# bytexplore_devboard.net
KiCad netlist of a schematic drawn in EAGLE
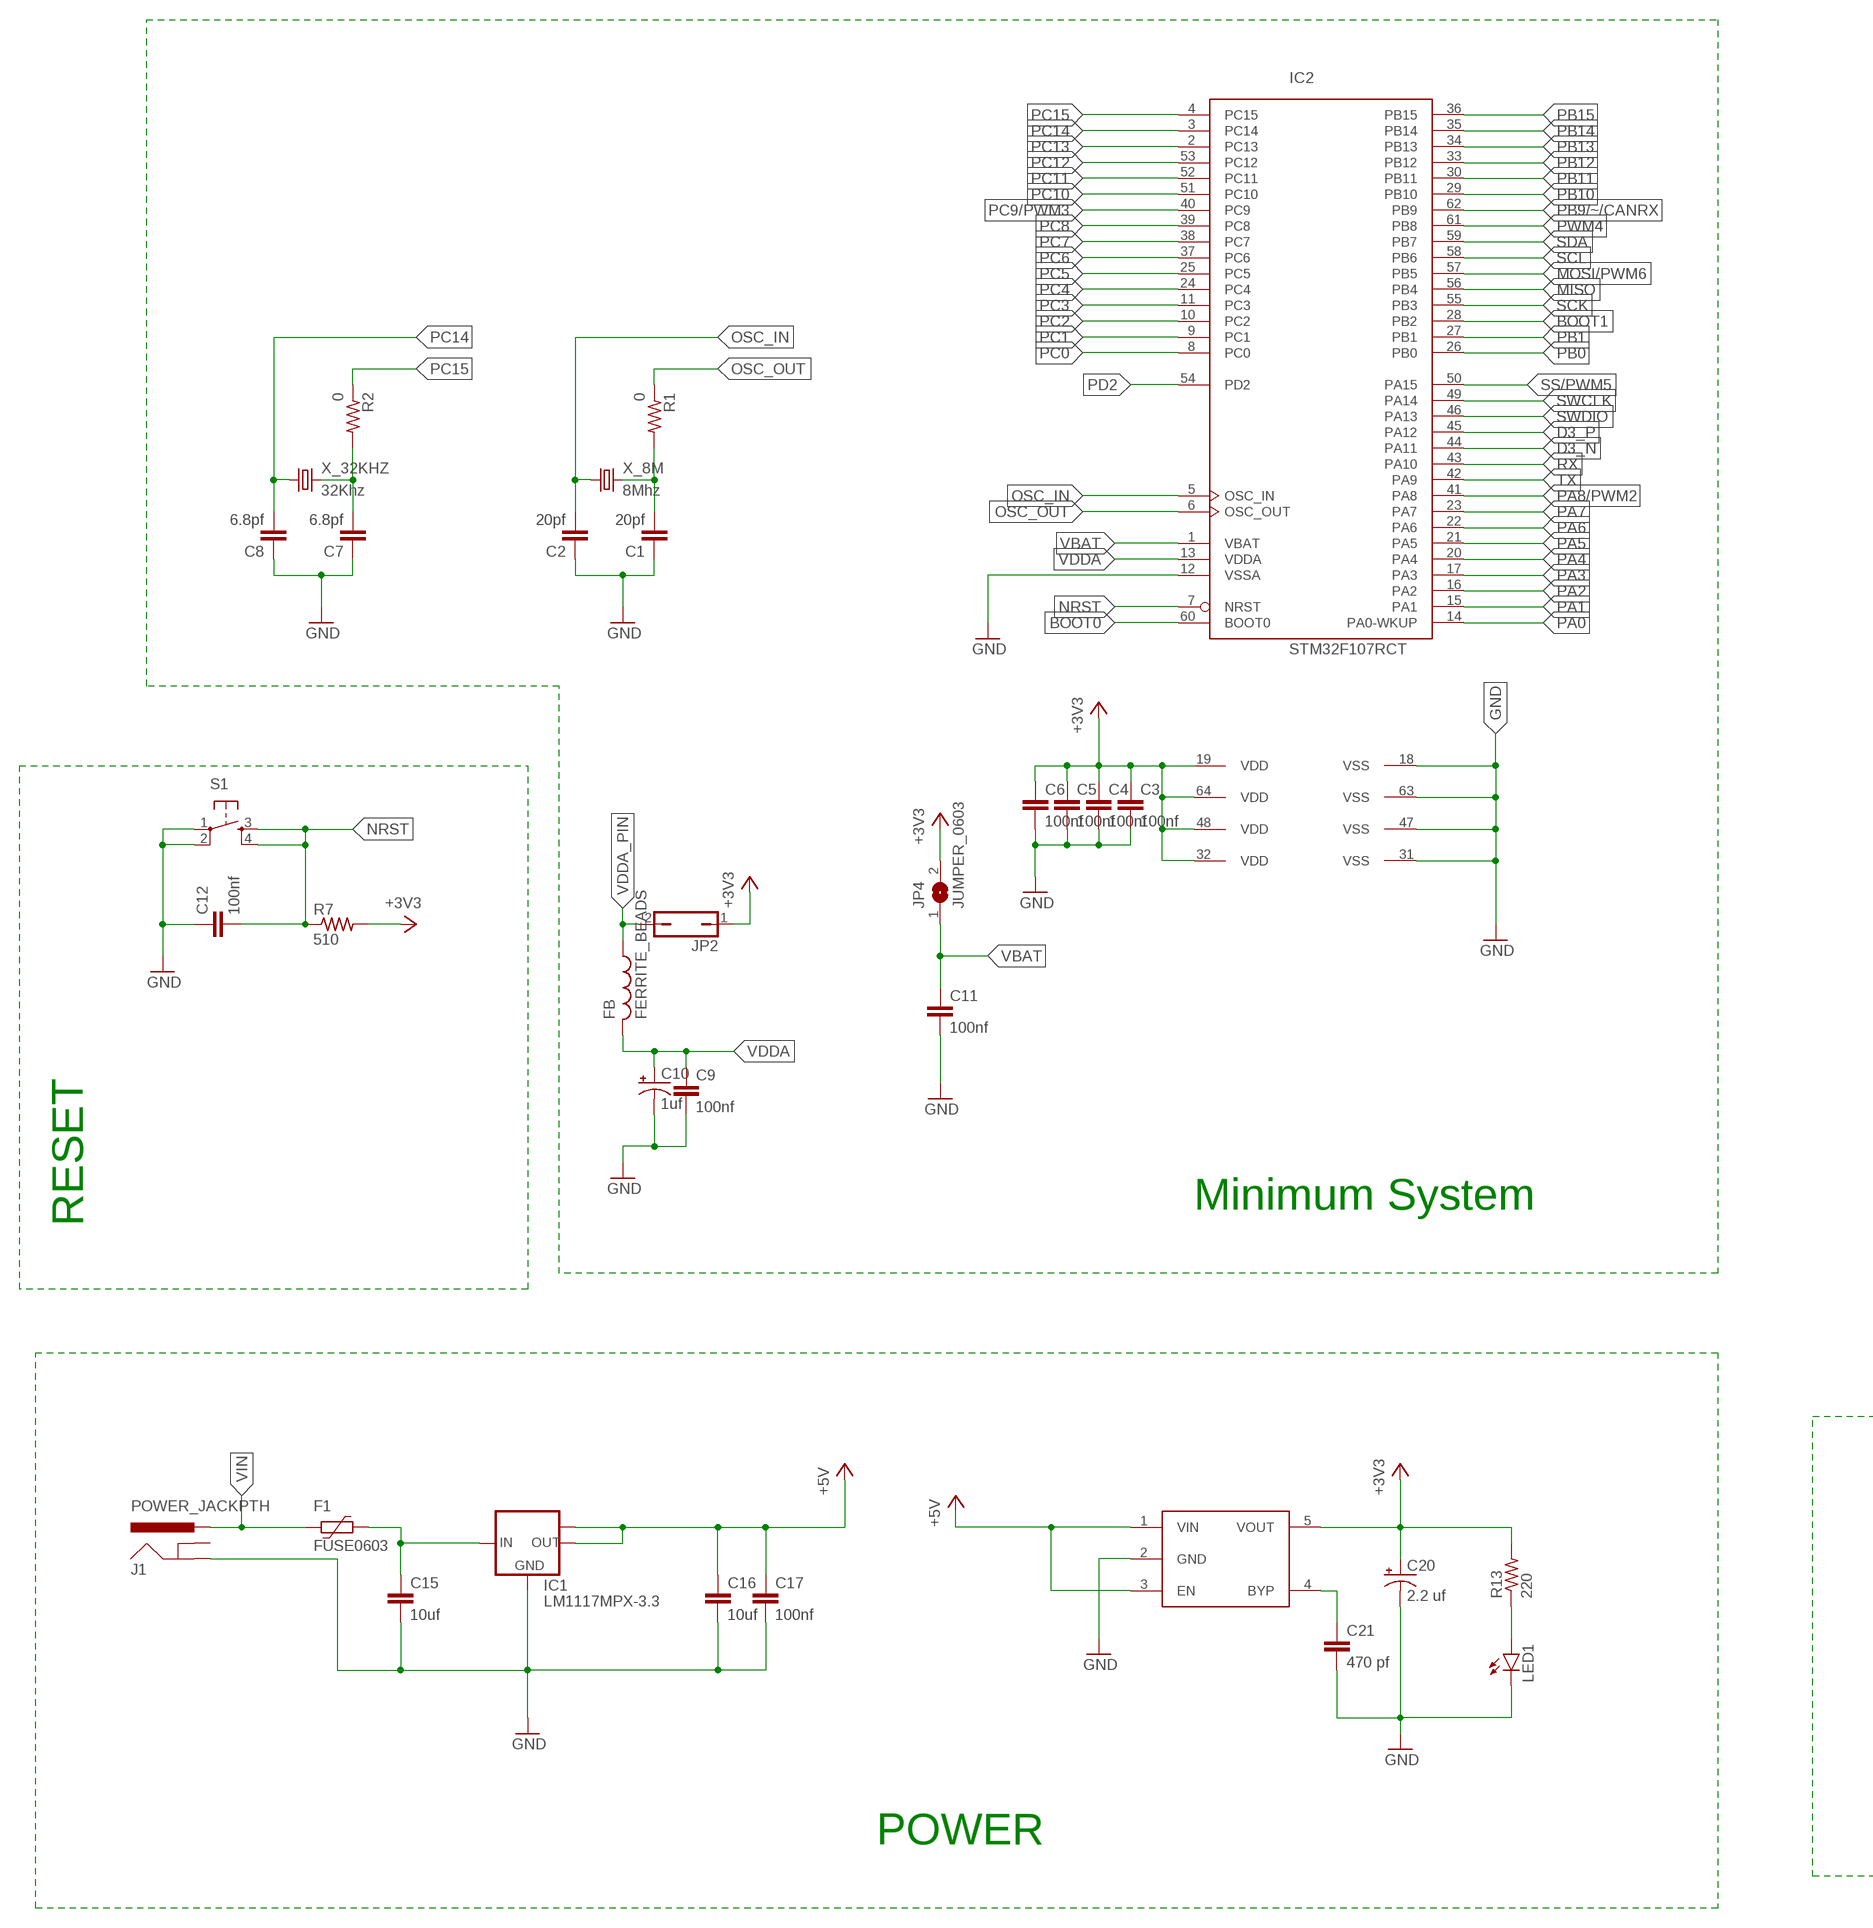
[diagram p0: schematic, sheet 1, part 1 of 2]
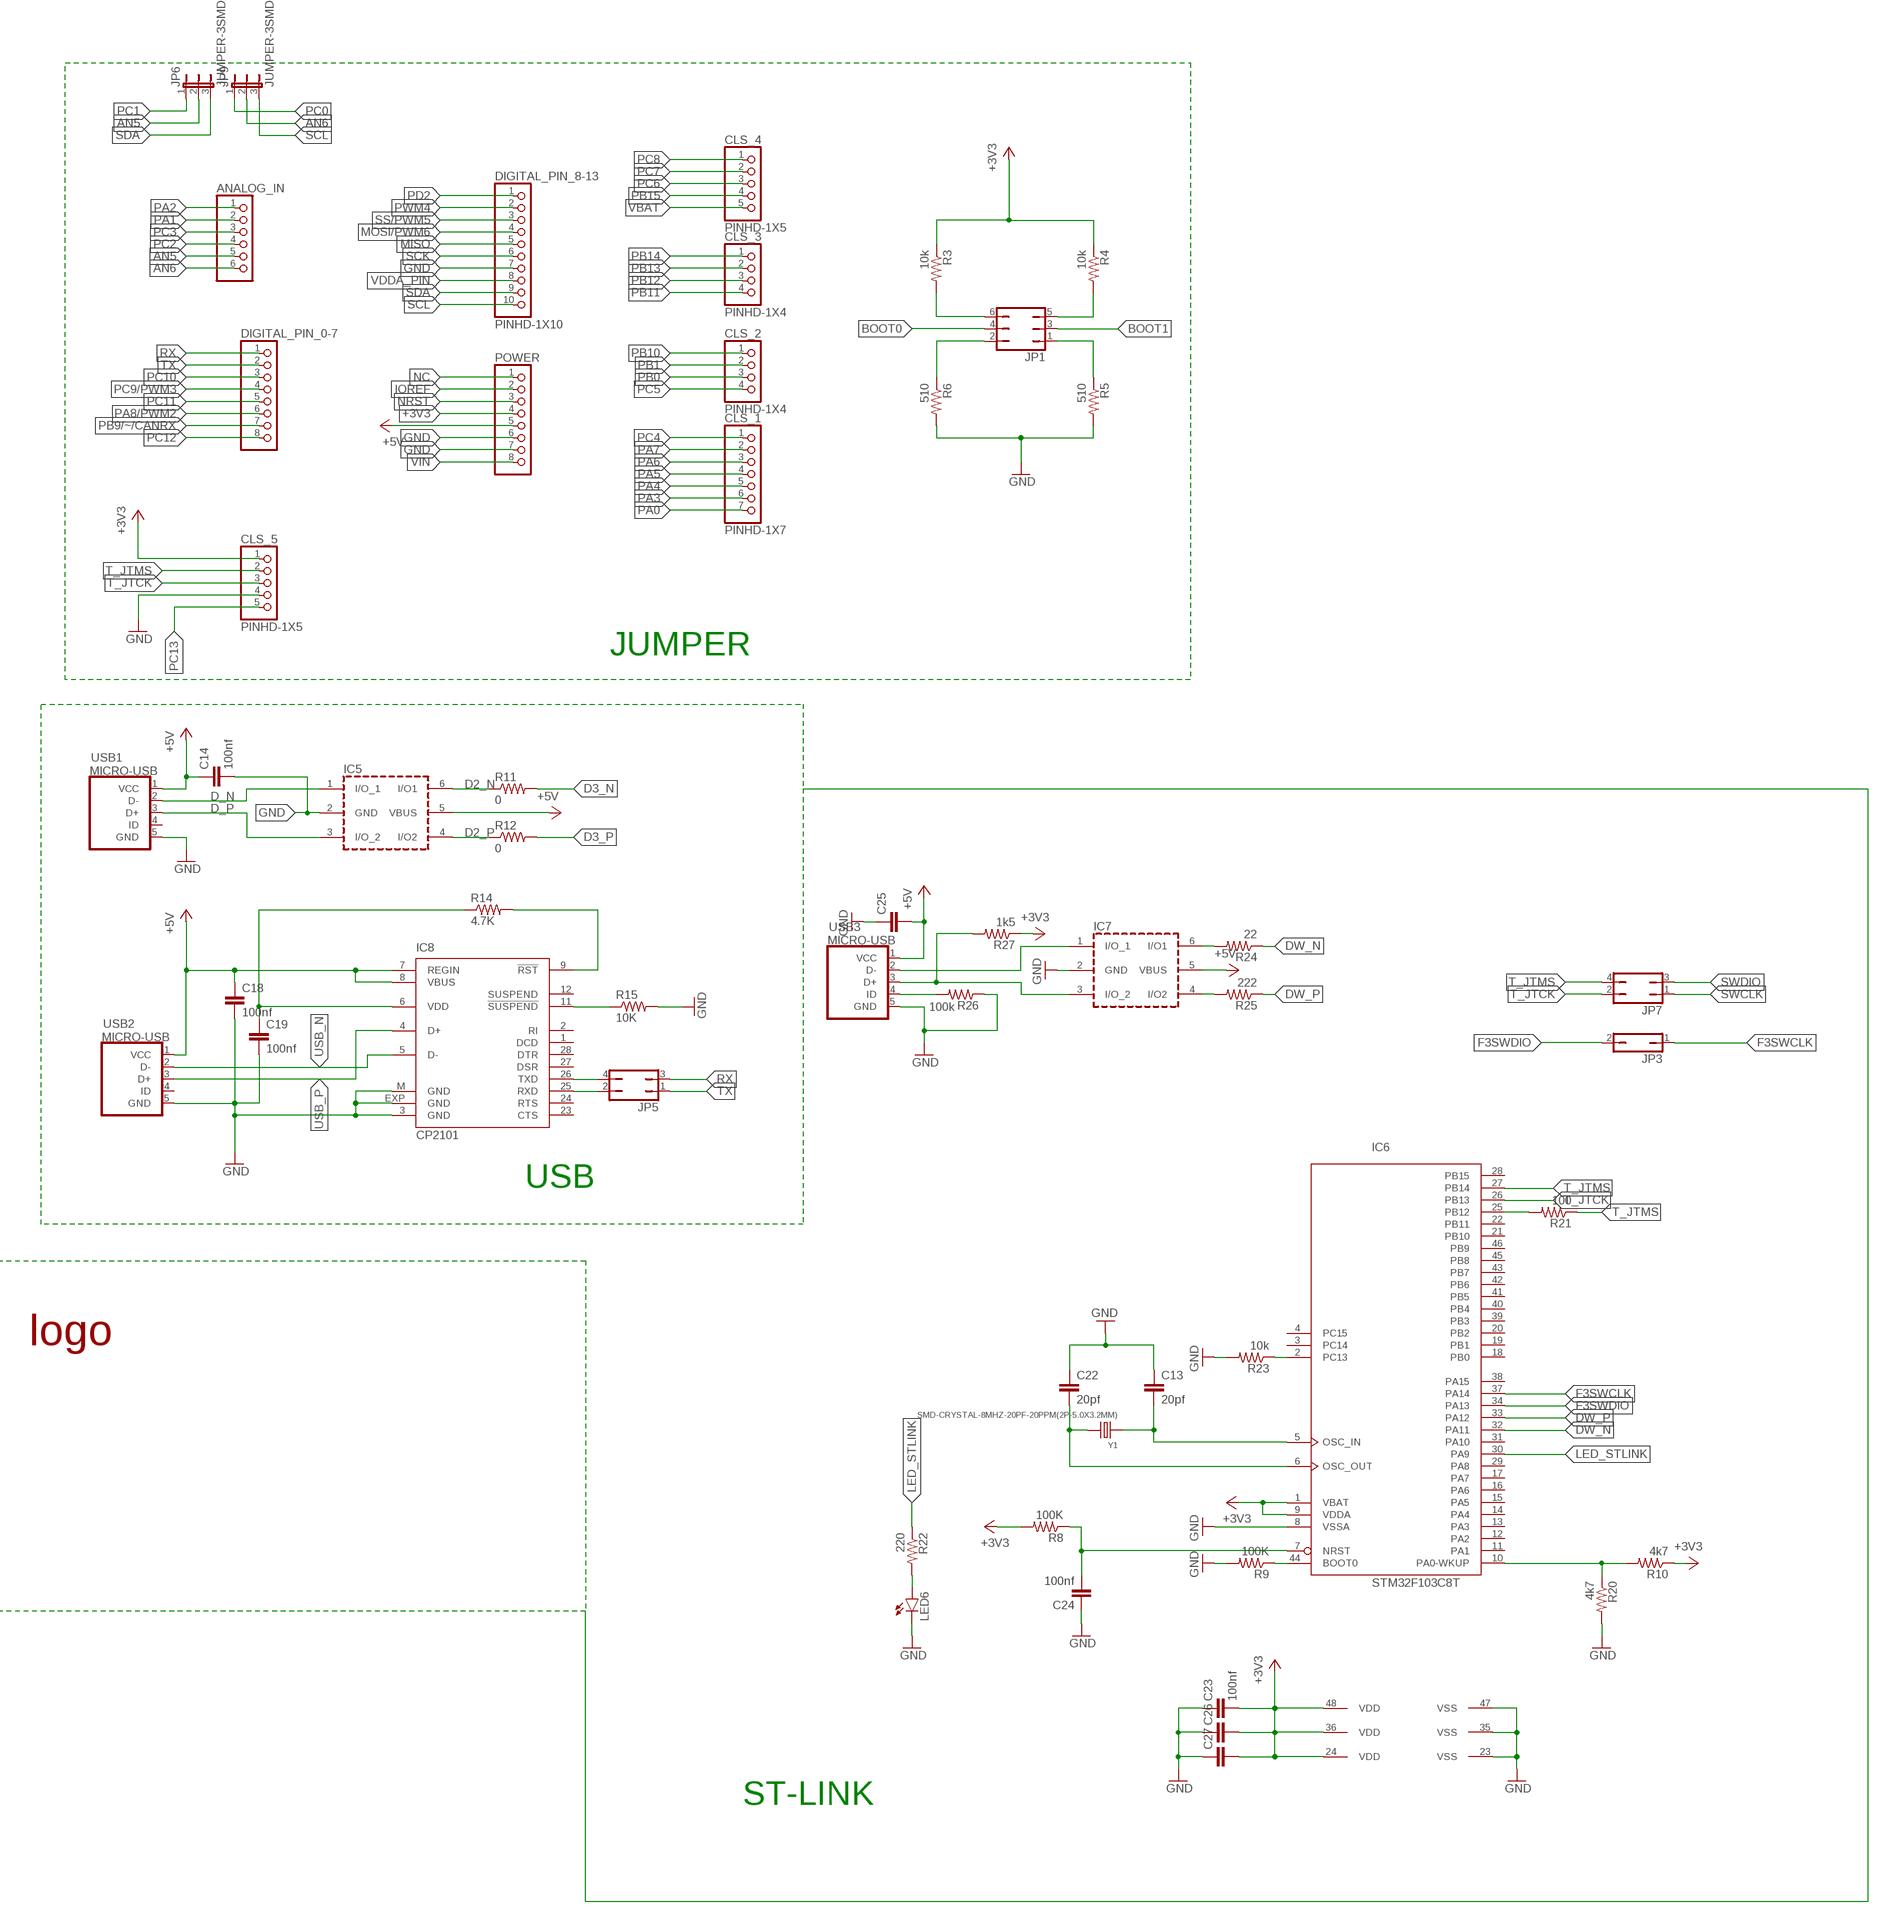
[diagram p1: schematic, sheet 1, part 2 of 2]

(export (version "E")
  (design (tool "Eeschema 10.0.6"))
  (components
    (comp (ref "ANALOG_IN")
      (value "PINHD-1X6B")
      (footprint "eagle-import:1X06-BIG")
      (libsource (lib "eagle-import") (part "PINHD-1X6B"))
    )
    (comp (ref "C1")
      (value "20pf")
      (footprint "eagle-import:C0603K")
      (libsource (lib "eagle-import") (part "C-EUC0603K"))
    )
    (comp (ref "C2")
      (value "20pf")
      (footprint "eagle-import:C0603K")
      (libsource (lib "eagle-import") (part "C-EUC0603K"))
    )
    (comp (ref "C3")
      (value "100nf")
      (footprint "eagle-import:C0603K")
      (libsource (lib "eagle-import") (part "C-EUC0603K"))
    )
    (comp (ref "C4")
      (value "100nf")
      (footprint "eagle-import:C0603K")
      (libsource (lib "eagle-import") (part "C-EUC0603K"))
    )
    (comp (ref "C5")
      (value "100nf")
      (footprint "eagle-import:C0603K")
      (libsource (lib "eagle-import") (part "C-EUC0603K"))
    )
    (comp (ref "C6")
      (value "100nf")
      (footprint "eagle-import:C0603K")
      (libsource (lib "eagle-import") (part "C-EUC0603K"))
    )
    (comp (ref "C7")
      (value "6.8pf")
      (footprint "eagle-import:C0603K")
      (libsource (lib "eagle-import") (part "C-EUC0603K"))
    )
    (comp (ref "C8")
      (value "6.8pf")
      (footprint "eagle-import:C0603K")
      (libsource (lib "eagle-import") (part "C-EUC0603K"))
    )
    (comp (ref "C9")
      (value "100nf")
      (footprint "eagle-import:C0603K")
      (libsource (lib "eagle-import") (part "C-EUC0603K"))
    )
    (comp (ref "C10")
      (value "1uf")
      (footprint "eagle-import:SMC_B")
      (libsource (lib "eagle-import") (part "CPOL-USSMCB"))
    )
    (comp (ref "C11")
      (value "100nf")
      (footprint "eagle-import:C0603K")
      (libsource (lib "eagle-import") (part "C-EUC0603K"))
    )
    (comp (ref "C12")
      (value "100nf")
      (footprint "eagle-import:C0603K")
      (libsource (lib "eagle-import") (part "C-EUC0603K"))
    )
    (comp (ref "C13")
      (value "20pf")
      (footprint "eagle-import:C0603")
      (libsource (lib "eagle-import") (part "C-EUC0603"))
    )
    (comp (ref "C14")
      (value "100nf")
      (footprint "eagle-import:C0603K")
      (libsource (lib "eagle-import") (part "C-EUC0603K"))
    )
    (comp (ref "C15")
      (value "10uf")
      (footprint "eagle-import:C0603")
      (libsource (lib "eagle-import") (part "C-EUC0603"))
    )
    (comp (ref "C16")
      (value "10uf")
      (footprint "eagle-import:C0603")
      (libsource (lib "eagle-import") (part "C-EUC0603"))
    )
    (comp (ref "C17")
      (value "100nf")
      (footprint "eagle-import:C0603")
      (libsource (lib "eagle-import") (part "C-EUC0603"))
    )
    (comp (ref "C18")
      (value "100nf")
      (footprint "eagle-import:C0603K")
      (libsource (lib "eagle-import") (part "C-EUC0603K"))
    )
    (comp (ref "C19")
      (value "100nf")
      (footprint "eagle-import:C0603K")
      (libsource (lib "eagle-import") (part "C-EUC0603K"))
    )
    (comp (ref "C20")
      (value "2.2 uf")
      (footprint "eagle-import:SMC_A")
      (libsource (lib "eagle-import") (part "CPOL-USSMCA"))
    )
    (comp (ref "C21")
      (value "470 pf")
      (footprint "eagle-import:C0603")
      (libsource (lib "eagle-import") (part "C-EUC0603"))
    )
    (comp (ref "C22")
      (value "20pf")
      (footprint "eagle-import:C0603")
      (libsource (lib "eagle-import") (part "C-EUC0603"))
    )
    (comp (ref "C23")
      (value "100nf")
      (footprint "eagle-import:C0603")
      (libsource (lib "eagle-import") (part "C-EUC0603"))
    )
    (comp (ref "C24")
      (value "100nf")
      (footprint "eagle-import:C0603")
      (libsource (lib "eagle-import") (part "C-EUC0603"))
    )
    (comp (ref "C25")
      (value "C-EUC0603")
      (footprint "eagle-import:C0603")
      (libsource (lib "eagle-import") (part "C-EUC0603"))
    )
    (comp (ref "C26")
      (value "C-EUC0603")
      (footprint "eagle-import:C0603")
      (libsource (lib "eagle-import") (part "C-EUC0603"))
    )
    (comp (ref "C27")
      (value "C-EUC0603")
      (footprint "eagle-import:C0603")
      (libsource (lib "eagle-import") (part "C-EUC0603"))
    )
    (comp (ref "CLS_1")
      (value "PINHD-1X7")
      (footprint "eagle-import:1X07-BIG")
      (libsource (lib "eagle-import") (part "PINHD-1X7"))
    )
    (comp (ref "CLS_2")
      (value "PINHD-1X4")
      (footprint "eagle-import:1X04-BIG")
      (libsource (lib "eagle-import") (part "PINHD-1X4"))
    )
    (comp (ref "CLS_3")
      (value "PINHD-1X4")
      (footprint "eagle-import:1X04-BIG")
      (libsource (lib "eagle-import") (part "PINHD-1X4"))
    )
    (comp (ref "CLS_4")
      (value "PINHD-1X5")
      (footprint "eagle-import:1X05-BIG")
      (libsource (lib "eagle-import") (part "PINHD-1X5"))
    )
    (comp (ref "CLS_5")
      (value "PINHD-1X5")
      (footprint "eagle-import:1X05-BIG")
      (libsource (lib "eagle-import") (part "PINHD-1X5"))
    )
    (comp (ref "DIGITAL_PIN_0-7")
      (value "PINHD-1X8BIG")
      (footprint "eagle-import:1X08-BIG")
      (libsource (lib "eagle-import") (part "PINHD-1X8BIG"))
    )
    (comp (ref "DIGITAL_PIN_8-13")
      (value "PINHD-1X10")
      (footprint "eagle-import:1X10-BIG")
      (libsource (lib "eagle-import") (part "PINHD-1X10"))
    )
    (comp (ref "F1")
      (value "FUSE0603")
      (footprint "eagle-import:R0603")
      (libsource (lib "eagle-import") (part "FUSE0603"))
    )
    (comp (ref "FB")
      (value "FERRITE_BEADS")
      (footprint "eagle-import:R0603")
      (libsource (lib "eagle-import") (part "FERRITE_BEADS"))
    )
    (comp (ref "IC1")
      (value "LM1117MPX-3.3")
      (footprint "eagle-import:SOT223")
      (libsource (lib "eagle-import") (part "LM1117MPX-3.3"))
    )
    (comp (ref "IC2")
      (value "STM32F107RCT")
      (footprint "eagle-import:LQFP64")
      (libsource (lib "eagle-import") (part "STM32F107RTC"))
    )
    (comp (ref "IC4")
      (value "MIC5219")
      (footprint "eagle-import:SOT-23-5")
      (libsource (lib "eagle-import") (part "MIC5219"))
    )
    (comp (ref "IC5")
      (value "USBLC6-2SC6")
      (footprint "eagle-import:SOT-23-6L")
      (libsource (lib "eagle-import") (part "USBLC6-2SC6"))
    )
    (comp (ref "IC6")
      (value "STM32F103C8T")
      (footprint "eagle-import:LQFP48")
      (libsource (lib "eagle-import") (part "STM32F103CT8"))
    )
    (comp (ref "IC7")
      (value "USBLC6-2SC6")
      (footprint "eagle-import:SOT-23-6L")
      (libsource (lib "eagle-import") (part "USBLC6-2SC6"))
    )
    (comp (ref "IC8")
      (value "CP2101")
      (footprint "eagle-import:MLP28")
      (libsource (lib "eagle-import") (part "CP2101"))
    )
    (comp (ref "J1")
      (value "POWER_JACKPTH")
      (footprint "eagle-import:POWER_JACK_PTH")
      (libsource (lib "eagle-import") (part "POWER_JACKPTH"))
    )
    (comp (ref "JP1")
      (value "JP3Q")
      (footprint "eagle-import:JP3Q")
      (libsource (lib "eagle-import") (part "JP3Q"))
    )
    (comp (ref "JP2")
      (value "JP1Q")
      (footprint "eagle-import:JP1")
      (libsource (lib "eagle-import") (part "JP1Q"))
    )
    (comp (ref "JP3")
      (value "JP1Q")
      (footprint "eagle-import:JP1")
      (libsource (lib "eagle-import") (part "JP1Q"))
    )
    (comp (ref "JP4")
      (value "JUMPER_0603")
      (footprint "eagle-import:R0603")
      (libsource (lib "eagle-import") (part "JUMPER_0603"))
    )
    (comp (ref "JP5")
      (value "JP2Q")
      (footprint "eagle-import:JP2Q")
      (libsource (lib "eagle-import") (part "JP2Q"))
    )
    (comp (ref "JP6")
      (value "JUMPER-3SMD")
      (footprint "eagle-import:SJ_3")
      (libsource (lib "eagle-import") (part "JUMPER-3SMD"))
    )
    (comp (ref "JP7")
      (value "JP2Q")
      (footprint "eagle-import:JP2Q")
      (libsource (lib "eagle-import") (part "JP2Q"))
    )
    (comp (ref "JP9")
      (value "JUMPER-3SMD")
      (footprint "eagle-import:SJ_3")
      (libsource (lib "eagle-import") (part "JUMPER-3SMD"))
    )
    (comp (ref "LED1")
      (value "LEDSML0603")
      (footprint "eagle-import:SML0603")
      (libsource (lib "eagle-import") (part "LEDSML0603"))
    )
    (comp (ref "LED6")
      (value "LEDSML0603")
      (footprint "eagle-import:SML0603")
      (libsource (lib "eagle-import") (part "LEDSML0603"))
    )
    (comp (ref "POWER")
      (value "PINHD-1X8BIG")
      (footprint "eagle-import:1X08-BIG")
      (libsource (lib "eagle-import") (part "PINHD-1X8BIG"))
    )
    (comp (ref "R1")
      (value "0")
      (footprint "eagle-import:R0603")
      (libsource (lib "eagle-import") (part "R-US_R0603"))
    )
    (comp (ref "R2")
      (value "0")
      (footprint "eagle-import:R0603")
      (libsource (lib "eagle-import") (part "R-US_R0603"))
    )
    (comp (ref "R3")
      (value "10k")
      (footprint "eagle-import:R0603")
      (libsource (lib "eagle-import") (part "R-US_R0603"))
    )
    (comp (ref "R4")
      (value "10k")
      (footprint "eagle-import:R0603")
      (libsource (lib "eagle-import") (part "R-US_R0603"))
    )
    (comp (ref "R5")
      (value "510")
      (footprint "eagle-import:R0603")
      (libsource (lib "eagle-import") (part "R-US_R0603"))
    )
    (comp (ref "R6")
      (value "510")
      (footprint "eagle-import:R0603")
      (libsource (lib "eagle-import") (part "R-US_R0603"))
    )
    (comp (ref "R7")
      (value "510")
      (footprint "eagle-import:R0603")
      (libsource (lib "eagle-import") (part "R-US_R0603"))
    )
    (comp (ref "R8")
      (value "100K")
      (footprint "eagle-import:R0603")
      (libsource (lib "eagle-import") (part "R-US_R0603"))
    )
    (comp (ref "R9")
      (value "100K")
      (footprint "eagle-import:R0603")
      (libsource (lib "eagle-import") (part "R-US_R0603"))
    )
    (comp (ref "R10")
      (value "4k7")
      (footprint "eagle-import:R0603")
      (libsource (lib "eagle-import") (part "R-US_R0603"))
    )
    (comp (ref "R11")
      (value "0")
      (footprint "eagle-import:R0603")
      (libsource (lib "eagle-import") (part "R-US_R0603"))
    )
    (comp (ref "R12")
      (value "0")
      (footprint "eagle-import:R0603")
      (libsource (lib "eagle-import") (part "R-US_R0603"))
    )
    (comp (ref "R13")
      (value "220")
      (footprint "eagle-import:R0603")
      (libsource (lib "eagle-import") (part "R-US_R0603"))
    )
    (comp (ref "R14")
      (value "4.7K")
      (footprint "eagle-import:R0603")
      (libsource (lib "eagle-import") (part "R-US_R0603"))
    )
    (comp (ref "R15")
      (value "10K")
      (footprint "eagle-import:R0603")
      (libsource (lib "eagle-import") (part "R-US_R0603"))
    )
    (comp (ref "R20")
      (value "4k7")
      (footprint "eagle-import:R0603")
      (libsource (lib "eagle-import") (part "R-US_R0603"))
    )
    (comp (ref "R21")
      (value "100")
      (footprint "eagle-import:R0603")
      (libsource (lib "eagle-import") (part "R-US_R0603"))
    )
    (comp (ref "R22")
      (value "220")
      (footprint "eagle-import:R0603")
      (libsource (lib "eagle-import") (part "R-US_R0603"))
    )
    (comp (ref "R23")
      (value "10k")
      (footprint "eagle-import:R0603")
      (libsource (lib "eagle-import") (part "R-US_R0603"))
    )
    (comp (ref "R24")
      (value "22")
      (footprint "eagle-import:R0603")
      (libsource (lib "eagle-import") (part "R-US_R0603"))
    )
    (comp (ref "R25")
      (value "222")
      (footprint "eagle-import:R0603")
      (libsource (lib "eagle-import") (part "R-US_R0603"))
    )
    (comp (ref "R26")
      (value "100k")
      (footprint "eagle-import:R0603")
      (libsource (lib "eagle-import") (part "R-US_R0603"))
    )
    (comp (ref "R27")
      (value "1k5")
      (footprint "eagle-import:R0603")
      (libsource (lib "eagle-import") (part "R-US_R0603"))
    )
    (comp (ref "S1")
      (value "TAC_SWITCHPTH")
      (footprint "eagle-import:TACTILE-PTH")
      (libsource (lib "eagle-import") (part "TAC_SWITCHPTH"))
    )
    (comp (ref "U$1")
      (value "LOGO_PME2")
      (footprint "eagle-import:LOGO_PME2")
      (libsource (lib "eagle-import") (part "LOGO_PME2"))
    )
    (comp (ref "USB1")
      (value "MICRO-USB")
      (footprint "eagle-import:MICRO-USB")
      (libsource (lib "eagle-import") (part "MICRO-USB"))
    )
    (comp (ref "USB2")
      (value "MICRO-USB")
      (footprint "eagle-import:MICRO-USB")
      (libsource (lib "eagle-import") (part "MICRO-USB"))
    )
    (comp (ref "USB3")
      (value "MICRO-USB")
      (footprint "eagle-import:MICRO-USB")
      (libsource (lib "eagle-import") (part "MICRO-USB"))
    )
    (comp (ref "X_8M")
      (value "8Mhz")
      (footprint "eagle-import:HC49U70")
      (libsource (lib "eagle-import") (part "CRYSTALHC49U70"))
    )
    (comp (ref "X_32KHZ")
      (value "32Khz")
      (footprint "eagle-import:TC26H")
      (libsource (lib "eagle-import") (part "CRYSTALTC26H"))
    )
    (comp (ref "Y1")
      (value "SMD-CRYSTAL-8MHZ-20PF-20PPM(2P-5.0X3.2MM)")
      (footprint "eagle-import:X2-SMD-5.0X3.2X1.3MM")
      (fields (field (name "MF") "Xinhunjing") (field (name "MP") "5032/4P"))
      (libsource (lib "eagle-import") (part "SMD-CRYSTAL-8MHZ-20PF-20PPM(2P-5.0X3.2MM)"))
    )
  )
  (nets
    (net (code "1") (name "+3V3") (class "Default")
      (node (ref "C20") (pin "+") (pinfunction "+_+") (pintype "passive"))
      (node (ref "C23") (pin "2") (pinfunction "2_2") (pintype "passive"))
      (node (ref "C26") (pin "2") (pinfunction "2_2") (pintype "passive"))
      (node (ref "C27") (pin "2") (pinfunction "2_2") (pintype "passive"))
      (node (ref "C3") (pin "1") (pinfunction "1_1") (pintype "passive"))
      (node (ref "C4") (pin "1") (pinfunction "1_1") (pintype "passive"))
      (node (ref "C5") (pin "1") (pinfunction "1_1") (pintype "passive"))
      (node (ref "C6") (pin "1") (pinfunction "1_1") (pintype "passive"))
      (node (ref "CLS_5") (pin "1") (pinfunction "1_1") (pintype "passive"))
      (node (ref "IC2") (pin "19") (pinfunction "VDD_19") (pintype "power_in"))
      (node (ref "IC2") (pin "32") (pinfunction "VDD_32") (pintype "power_in"))
      (node (ref "IC2") (pin "48") (pinfunction "VDD_48") (pintype "power_in"))
      (node (ref "IC2") (pin "64") (pinfunction "VDD_64") (pintype "power_in"))
      (node (ref "IC4") (pin "5") (pinfunction "VOUT_5") (pintype "bidirectional"))
      (node (ref "IC6") (pin "1") (pinfunction "VBAT_1") (pintype "power_in"))
      (node (ref "IC6") (pin "24") (pinfunction "VDD_24") (pintype "power_in"))
      (node (ref "IC6") (pin "36") (pinfunction "VDD_36") (pintype "power_in"))
      (node (ref "IC6") (pin "48") (pinfunction "VDD_48") (pintype "power_in"))
      (node (ref "IC6") (pin "9") (pinfunction "VDDA_9") (pintype "power_in"))
      (node (ref "JP2") (pin "1") (pinfunction "1_1") (pintype "passive"))
      (node (ref "JP4") (pin "2") (pinfunction "2_2") (pintype "passive"))
      (node (ref "POWER") (pin "4") (pinfunction "4_4") (pintype "passive"))
      (node (ref "R10") (pin "1") (pinfunction "1_1") (pintype "passive"))
      (node (ref "R13") (pin "2") (pinfunction "2_2") (pintype "passive"))
      (node (ref "R27") (pin "1") (pinfunction "1_1") (pintype "passive"))
      (node (ref "R3") (pin "1") (pinfunction "1_1") (pintype "passive"))
      (node (ref "R4") (pin "1") (pinfunction "1_1") (pintype "passive"))
      (node (ref "R7") (pin "2") (pinfunction "2_2") (pintype "passive"))
      (node (ref "R8") (pin "2") (pinfunction "2_2") (pintype "passive"))
    )
    (net (code "2") (name "+5V") (class "Default")
      (node (ref "C14") (pin "1") (pinfunction "1_1") (pintype "passive"))
      (node (ref "C16") (pin "1") (pinfunction "1_1") (pintype "passive"))
      (node (ref "C17") (pin "1") (pinfunction "1_1") (pintype "passive"))
      (node (ref "C18") (pin "1") (pinfunction "1_1") (pintype "passive"))
      (node (ref "C25") (pin "2") (pinfunction "2_2") (pintype "passive"))
      (node (ref "IC1") (pin "2") (pinfunction "OUT_2") (pintype "passive"))
      (node (ref "IC1") (pin "TAB") (pinfunction "OUT1_TAB") (pintype "passive"))
      (node (ref "IC4") (pin "1") (pinfunction "VIN_1") (pintype "bidirectional"))
      (node (ref "IC4") (pin "3") (pinfunction "EN_3") (pintype "bidirectional"))
      (node (ref "IC5") (pin "5") (pinfunction "VBUS_5") (pintype "bidirectional"))
      (node (ref "IC7") (pin "5") (pinfunction "VBUS_5") (pintype "bidirectional"))
      (node (ref "IC8") (pin "7") (pinfunction "REGIN_7") (pintype "passive"))
      (node (ref "IC8") (pin "8") (pinfunction "VBUS_8") (pintype "input"))
      (node (ref "POWER") (pin "5") (pinfunction "5_5") (pintype "passive"))
      (node (ref "USB1") (pin "1") (pinfunction "VCC_1") (pintype "power_in"))
      (node (ref "USB2") (pin "1") (pinfunction "VCC_1") (pintype "power_in"))
      (node (ref "USB3") (pin "1") (pinfunction "VCC_1") (pintype "power_in"))
    )
    (net (code "3") (name "/D2_N") (class "Default")
      (node (ref "IC5") (pin "6") (pinfunction "I/O1_6") (pintype "bidirectional"))
      (node (ref "R11") (pin "1") (pinfunction "1_1") (pintype "passive"))
    )
    (net (code "4") (name "/D2_P") (class "Default")
      (node (ref "IC5") (pin "4") (pinfunction "I/O2_4") (pintype "bidirectional"))
      (node (ref "R12") (pin "1") (pinfunction "1_1") (pintype "passive"))
    )
    (net (code "5") (name "/D_N") (class "Default")
      (node (ref "IC5") (pin "1") (pinfunction "I/O_1_1") (pintype "bidirectional"))
      (node (ref "USB1") (pin "2") (pinfunction "D-_2") (pintype "bidirectional"))
    )
    (net (code "6") (name "/D_P") (class "Default")
      (node (ref "IC5") (pin "3") (pinfunction "I/O_2_3") (pintype "bidirectional"))
      (node (ref "USB1") (pin "3") (pinfunction "D+_3") (pintype "bidirectional"))
    )
    (net (code "7") (name "/PB9{slash}~{{slash}CANRX}") (class "Default")
      (node (ref "DIGITAL_PIN_0-7") (pin "7") (pinfunction "7_7") (pintype "passive"))
      (node (ref "IC2") (pin "62") (pinfunction "PB9_62") (pintype "bidirectional"))
    )
    (net (code "8") (name "AN5") (class "Default")
      (node (ref "ANALOG_IN") (pin "5") (pinfunction "5_5") (pintype "passive"))
      (node (ref "JP6") (pin "2") (pinfunction "2_2") (pintype "passive"))
    )
    (net (code "9") (name "AN6") (class "Default")
      (node (ref "ANALOG_IN") (pin "6") (pinfunction "6_6") (pintype "passive"))
      (node (ref "JP9") (pin "2") (pinfunction "2_2") (pintype "passive"))
    )
    (net (code "10") (name "BOOT0") (class "Default")
      (node (ref "IC2") (pin "60") (pinfunction "BOOT0_60") (pintype "input"))
      (node (ref "JP1") (pin "4") (pinfunction "4_4") (pintype "passive"))
    )
    (net (code "11") (name "BOOT1") (class "Default")
      (node (ref "IC2") (pin "28") (pinfunction "PB2_28") (pintype "bidirectional"))
      (node (ref "JP1") (pin "3") (pinfunction "3_3") (pintype "passive"))
    )
    (net (code "12") (name "D3_N") (class "Default")
      (node (ref "IC2") (pin "44") (pinfunction "PA11_44") (pintype "bidirectional"))
      (node (ref "R11") (pin "2") (pinfunction "2_2") (pintype "passive"))
    )
    (net (code "13") (name "D3_P") (class "Default")
      (node (ref "IC2") (pin "45") (pinfunction "PA12_45") (pintype "bidirectional"))
      (node (ref "R12") (pin "2") (pinfunction "2_2") (pintype "passive"))
    )
    (net (code "14") (name "DW_N") (class "Default")
      (node (ref "IC6") (pin "32") (pinfunction "PA11_32") (pintype "bidirectional"))
      (node (ref "R24") (pin "1") (pinfunction "1_1") (pintype "passive"))
    )
    (net (code "15") (name "DW_P") (class "Default")
      (node (ref "IC6") (pin "33") (pinfunction "PA12_33") (pintype "bidirectional"))
      (node (ref "R25") (pin "1") (pinfunction "1_1") (pintype "passive"))
    )
    (net (code "16") (name "F3SWCLK") (class "Default")
      (node (ref "IC6") (pin "37") (pinfunction "PA14_37") (pintype "bidirectional"))
      (node (ref "JP3") (pin "1") (pinfunction "1_1") (pintype "passive"))
    )
    (net (code "17") (name "F3SWDIO") (class "Default")
      (node (ref "IC6") (pin "34") (pinfunction "PA13_34") (pintype "bidirectional"))
      (node (ref "JP3") (pin "2") (pinfunction "2_2") (pintype "passive"))
    )
    (net (code "18") (name "GND") (class "Default")
      (node (ref "C1") (pin "1") (pinfunction "1_1") (pintype "passive"))
      (node (ref "C10") (pin "-") (pinfunction "-_-") (pintype "passive"))
      (node (ref "C11") (pin "2") (pinfunction "2_2") (pintype "passive"))
      (node (ref "C12") (pin "1") (pinfunction "1_1") (pintype "passive"))
      (node (ref "C13") (pin "1") (pinfunction "1_1") (pintype "passive"))
      (node (ref "C14") (pin "2") (pinfunction "2_2") (pintype "passive"))
      (node (ref "C15") (pin "2") (pinfunction "2_2") (pintype "passive"))
      (node (ref "C16") (pin "2") (pinfunction "2_2") (pintype "passive"))
      (node (ref "C17") (pin "2") (pinfunction "2_2") (pintype "passive"))
      (node (ref "C18") (pin "2") (pinfunction "2_2") (pintype "passive"))
      (node (ref "C19") (pin "2") (pinfunction "2_2") (pintype "passive"))
      (node (ref "C2") (pin "1") (pinfunction "1_1") (pintype "passive"))
      (node (ref "C20") (pin "-") (pinfunction "-_-") (pintype "passive"))
      (node (ref "C21") (pin "2") (pinfunction "2_2") (pintype "passive"))
      (node (ref "C22") (pin "1") (pinfunction "1_1") (pintype "passive"))
      (node (ref "C23") (pin "1") (pinfunction "1_1") (pintype "passive"))
      (node (ref "C24") (pin "1") (pinfunction "1_1") (pintype "passive"))
      (node (ref "C25") (pin "1") (pinfunction "1_1") (pintype "passive"))
      (node (ref "C26") (pin "1") (pinfunction "1_1") (pintype "passive"))
      (node (ref "C27") (pin "1") (pinfunction "1_1") (pintype "passive"))
      (node (ref "C3") (pin "2") (pinfunction "2_2") (pintype "passive"))
      (node (ref "C4") (pin "2") (pinfunction "2_2") (pintype "passive"))
      (node (ref "C5") (pin "2") (pinfunction "2_2") (pintype "passive"))
      (node (ref "C6") (pin "2") (pinfunction "2_2") (pintype "passive"))
      (node (ref "C7") (pin "1") (pinfunction "1_1") (pintype "passive"))
      (node (ref "C8") (pin "1") (pinfunction "1_1") (pintype "passive"))
      (node (ref "C9") (pin "2") (pinfunction "2_2") (pintype "passive"))
      (node (ref "CLS_5") (pin "4") (pinfunction "4_4") (pintype "passive"))
      (node (ref "DIGITAL_PIN_8-13") (pin "7") (pinfunction "7_7") (pintype "passive"))
      (node (ref "IC1") (pin "1") (pinfunction "GND_1") (pintype "input"))
      (node (ref "IC2") (pin "12") (pinfunction "VSSA_12") (pintype "power_in"))
      (node (ref "IC2") (pin "18") (pinfunction "VSS_18") (pintype "power_in"))
      (node (ref "IC2") (pin "31") (pinfunction "VSS_31") (pintype "power_in"))
      (node (ref "IC2") (pin "47") (pinfunction "VSS_47") (pintype "power_in"))
      (node (ref "IC2") (pin "63") (pinfunction "VSS_63") (pintype "power_in"))
      (node (ref "IC4") (pin "2") (pinfunction "GND_2") (pintype "bidirectional"))
      (node (ref "IC5") (pin "2") (pinfunction "GND_2") (pintype "bidirectional"))
      (node (ref "IC6") (pin "23") (pinfunction "VSS_23") (pintype "power_in"))
      (node (ref "IC6") (pin "35") (pinfunction "VSS_35") (pintype "power_in"))
      (node (ref "IC6") (pin "47") (pinfunction "VSS_47") (pintype "power_in"))
      (node (ref "IC6") (pin "8") (pinfunction "VSSA_8") (pintype "power_in"))
      (node (ref "IC7") (pin "2") (pinfunction "GND_2") (pintype "bidirectional"))
      (node (ref "IC8") (pin "3") (pinfunction "GND_3") (pintype "power_in"))
      (node (ref "IC8") (pin "EXP") (pinfunction "GND_EXP") (pintype "power_in"))
      (node (ref "IC8") (pin "M") (pinfunction "GND_M") (pintype "power_in"))
      (node (ref "J1") (pin "GND") (pinfunction "GND_GND") (pintype "bidirectional"))
      (node (ref "LED1") (pin "C") (pinfunction "C_C") (pintype "passive"))
      (node (ref "LED6") (pin "C") (pinfunction "C_C") (pintype "passive"))
      (node (ref "POWER") (pin "6") (pinfunction "6_6") (pintype "passive"))
      (node (ref "POWER") (pin "7") (pinfunction "7_7") (pintype "passive"))
      (node (ref "R15") (pin "2") (pinfunction "2_2") (pintype "passive"))
      (node (ref "R20") (pin "2") (pinfunction "2_2") (pintype "passive"))
      (node (ref "R23") (pin "2") (pinfunction "2_2") (pintype "passive"))
      (node (ref "R26") (pin "1") (pinfunction "1_1") (pintype "passive"))
      (node (ref "R5") (pin "2") (pinfunction "2_2") (pintype "passive"))
      (node (ref "R6") (pin "2") (pinfunction "2_2") (pintype "passive"))
      (node (ref "R9") (pin "2") (pinfunction "2_2") (pintype "passive"))
      (node (ref "S1") (pin "1") (pinfunction "1_1") (pintype "passive"))
      (node (ref "S1") (pin "2") (pinfunction "2_2") (pintype "passive"))
      (node (ref "USB1") (pin "5") (pinfunction "GND_5") (pintype "power_in"))
      (node (ref "USB2") (pin "5") (pinfunction "GND_5") (pintype "power_in"))
      (node (ref "USB3") (pin "5") (pinfunction "GND_5") (pintype "power_in"))
    )
    (net (code "19") (name "IOREF") (class "Default")
      (node (ref "POWER") (pin "2") (pinfunction "2_2") (pintype "passive"))
    )
    (net (code "20") (name "LED_STLINK") (class "Default")
      (node (ref "IC6") (pin "30") (pinfunction "PA9_30") (pintype "bidirectional"))
      (node (ref "R22") (pin "1") (pinfunction "1_1") (pintype "passive"))
    )
    (net (code "21") (name "MISO") (class "Default")
      (node (ref "DIGITAL_PIN_8-13") (pin "5") (pinfunction "5_5") (pintype "passive"))
      (node (ref "IC2") (pin "56") (pinfunction "PB4_56") (pintype "bidirectional"))
    )
    (net (code "22") (name "MOSI{slash}PWM6") (class "Default")
      (node (ref "DIGITAL_PIN_8-13") (pin "4") (pinfunction "4_4") (pintype "passive"))
      (node (ref "IC2") (pin "57") (pinfunction "PB5_57") (pintype "bidirectional"))
    )
    (net (code "23") (name "NC") (class "Default")
      (node (ref "POWER") (pin "1") (pinfunction "1_1") (pintype "passive"))
    )
    (net (code "24") (name "NRST") (class "Default")
      (node (ref "C12") (pin "2") (pinfunction "2_2") (pintype "passive"))
      (node (ref "IC2") (pin "7") (pinfunction "NRST_7") (pintype "bidirectional"))
      (node (ref "POWER") (pin "3") (pinfunction "3_3") (pintype "passive"))
      (node (ref "R7") (pin "1") (pinfunction "1_1") (pintype "passive"))
      (node (ref "S1") (pin "3") (pinfunction "3_3") (pintype "passive"))
      (node (ref "S1") (pin "4") (pinfunction "4_4") (pintype "passive"))
    )
    (net (code "25") (name "Net-(C1-Pad2)") (class "Default")
      (node (ref "C1") (pin "2") (pinfunction "2_2") (pintype "passive"))
      (node (ref "R1") (pin "2") (pinfunction "2_2") (pintype "passive"))
      (node (ref "X_8M") (pin "2") (pinfunction "2_2") (pintype "passive"))
    )
    (net (code "26") (name "Net-(C7-Pad2)") (class "Default")
      (node (ref "C7") (pin "2") (pinfunction "2_2") (pintype "passive"))
      (node (ref "R2") (pin "2") (pinfunction "2_2") (pintype "passive"))
      (node (ref "X_32KHZ") (pin "2") (pinfunction "2_2") (pintype "passive"))
    )
    (net (code "27") (name "Net-(IC1-IN)") (class "Default")
      (node (ref "C15") (pin "1") (pinfunction "1_1") (pintype "passive"))
      (node (ref "F1") (pin "1") (pinfunction "1_1") (pintype "passive"))
      (node (ref "IC1") (pin "3") (pinfunction "IN_3") (pintype "input"))
    )
    (net (code "28") (name "Net-(IC4-BYP)") (class "Default")
      (node (ref "C21") (pin "1") (pinfunction "1_1") (pintype "passive"))
      (node (ref "IC4") (pin "4") (pinfunction "BYP_4") (pintype "bidirectional"))
    )
    (net (code "29") (name "Net-(IC6A-BOOT0)") (class "Default")
      (node (ref "IC6") (pin "44") (pinfunction "BOOT0_44") (pintype "input"))
      (node (ref "R9") (pin "1") (pinfunction "1_1") (pintype "passive"))
    )
    (net (code "30") (name "Net-(IC6A-NRST)") (class "Default")
      (node (ref "C24") (pin "2") (pinfunction "2_2") (pintype "passive"))
      (node (ref "IC6") (pin "7") (pinfunction "NRST_7") (pintype "bidirectional"))
      (node (ref "R8") (pin "1") (pinfunction "1_1") (pintype "passive"))
    )
    (net (code "31") (name "Net-(IC6A-OSC_IN)") (class "Default")
      (node (ref "C13") (pin "2") (pinfunction "2_2") (pintype "passive"))
      (node (ref "IC6") (pin "5") (pinfunction "OSC_IN_5") (pintype "bidirectional"))
      (node (ref "Y1") (pin "1") (pinfunction "1_1") (pintype "passive"))
    )
    (net (code "32") (name "Net-(IC6A-OSC_OUT)") (class "Default")
      (node (ref "C22") (pin "2") (pinfunction "2_2") (pintype "passive"))
      (node (ref "IC6") (pin "6") (pinfunction "OSC_OUT_6") (pintype "bidirectional"))
      (node (ref "Y1") (pin "2") (pinfunction "2_2") (pintype "passive"))
    )
    (net (code "33") (name "Net-(IC6A-PA0-WKUP)") (class "Default")
      (node (ref "IC6") (pin "10") (pinfunction "PA0-WKUP_10") (pintype "bidirectional"))
      (node (ref "R10") (pin "2") (pinfunction "2_2") (pintype "passive"))
      (node (ref "R20") (pin "1") (pinfunction "1_1") (pintype "passive"))
    )
    (net (code "34") (name "Net-(IC6A-PB12)") (class "Default")
      (node (ref "IC6") (pin "25") (pinfunction "PB12_25") (pintype "bidirectional"))
      (node (ref "R21") (pin "2") (pinfunction "2_2") (pintype "passive"))
    )
    (net (code "35") (name "Net-(IC6A-PC13)") (class "Default")
      (node (ref "IC6") (pin "2") (pinfunction "PC13_2") (pintype "bidirectional"))
      (node (ref "R23") (pin "1") (pinfunction "1_1") (pintype "passive"))
    )
    (net (code "36") (name "Net-(IC7-I{slash}O1)") (class "Default")
      (node (ref "IC7") (pin "6") (pinfunction "I/O1_6") (pintype "bidirectional"))
      (node (ref "R24") (pin "2") (pinfunction "2_2") (pintype "passive"))
    )
    (net (code "37") (name "Net-(IC7-I{slash}O2)") (class "Default")
      (node (ref "IC7") (pin "4") (pinfunction "I/O2_4") (pintype "bidirectional"))
      (node (ref "R25") (pin "2") (pinfunction "2_2") (pintype "passive"))
    )
    (net (code "38") (name "Net-(IC7-I{slash}O_1)") (class "Default")
      (node (ref "IC7") (pin "1") (pinfunction "I/O_1_1") (pintype "bidirectional"))
      (node (ref "USB3") (pin "2") (pinfunction "D-_2") (pintype "bidirectional"))
    )
    (net (code "39") (name "Net-(IC7-I{slash}O_2)") (class "Default")
      (node (ref "IC7") (pin "3") (pinfunction "I/O_2_3") (pintype "bidirectional"))
      (node (ref "R27") (pin "2") (pinfunction "2_2") (pintype "passive"))
      (node (ref "USB3") (pin "3") (pinfunction "D+_3") (pintype "bidirectional"))
    )
    (net (code "40") (name "Net-(IC8-RXD)") (class "Default")
      (node (ref "IC8") (pin "25") (pinfunction "RXD_25") (pintype "input"))
      (node (ref "JP5") (pin "2") (pinfunction "2_2") (pintype "passive"))
    )
    (net (code "41") (name "Net-(IC8-TXD)") (class "Default")
      (node (ref "IC8") (pin "26") (pinfunction "TXD_26") (pintype "output"))
      (node (ref "JP5") (pin "4") (pinfunction "4_4") (pintype "passive"))
    )
    (net (code "42") (name "Net-(IC8-VDD)") (class "Default")
      (node (ref "C19") (pin "1") (pinfunction "1_1") (pintype "passive"))
      (node (ref "IC8") (pin "6") (pinfunction "VDD_6") (pintype "power_in"))
      (node (ref "R14") (pin "1") (pinfunction "1_1") (pintype "passive"))
    )
    (net (code "43") (name "Net-(IC8-~{RST})") (class "Default")
      (node (ref "IC8") (pin "9") (pinfunction "~{RST}_9") (pintype "bidirectional"))
      (node (ref "R14") (pin "2") (pinfunction "2_2") (pintype "passive"))
    )
    (net (code "44") (name "Net-(IC8-~{SUSPEND})") (class "Default")
      (node (ref "IC8") (pin "11") (pinfunction "~{SUSPEND}_11") (pintype "output"))
      (node (ref "R15") (pin "1") (pinfunction "1_1") (pintype "passive"))
    )
    (net (code "45") (name "Net-(JP1-Pad1)") (class "Default")
      (node (ref "JP1") (pin "1") (pinfunction "1_1") (pintype "passive"))
      (node (ref "R5") (pin "1") (pinfunction "1_1") (pintype "passive"))
    )
    (net (code "46") (name "Net-(JP1-Pad2)") (class "Default")
      (node (ref "JP1") (pin "2") (pinfunction "2_2") (pintype "passive"))
      (node (ref "R6") (pin "1") (pinfunction "1_1") (pintype "passive"))
    )
    (net (code "47") (name "Net-(JP1-Pad5)") (class "Default")
      (node (ref "JP1") (pin "5") (pinfunction "5_5") (pintype "passive"))
      (node (ref "R4") (pin "2") (pinfunction "2_2") (pintype "passive"))
    )
    (net (code "48") (name "Net-(JP1-Pad6)") (class "Default")
      (node (ref "JP1") (pin "6") (pinfunction "6_6") (pintype "passive"))
      (node (ref "R3") (pin "2") (pinfunction "2_2") (pintype "passive"))
    )
    (net (code "49") (name "Net-(LED1-PadA)") (class "Default")
      (node (ref "LED1") (pin "A") (pinfunction "A_A") (pintype "passive"))
      (node (ref "R13") (pin "1") (pinfunction "1_1") (pintype "passive"))
    )
    (net (code "50") (name "Net-(LED6-PadA)") (class "Default")
      (node (ref "LED6") (pin "A") (pinfunction "A_A") (pintype "passive"))
      (node (ref "R22") (pin "2") (pinfunction "2_2") (pintype "passive"))
    )
    (net (code "51") (name "Net-(USB3-ID)") (class "Default")
      (node (ref "R26") (pin "2") (pinfunction "2_2") (pintype "passive"))
      (node (ref "USB3") (pin "4") (pinfunction "ID_4") (pintype "bidirectional"))
    )
    (net (code "52") (name "OSC_IN") (class "Default")
      (node (ref "C2") (pin "2") (pinfunction "2_2") (pintype "passive"))
      (node (ref "IC2") (pin "5") (pinfunction "OSC_IN_5") (pintype "bidirectional"))
      (node (ref "X_8M") (pin "1") (pinfunction "1_1") (pintype "passive"))
    )
    (net (code "53") (name "OSC_OUT") (class "Default")
      (node (ref "IC2") (pin "6") (pinfunction "OSC_OUT_6") (pintype "bidirectional"))
      (node (ref "R1") (pin "1") (pinfunction "1_1") (pintype "passive"))
    )
    (net (code "54") (name "PA0") (class "Default")
      (node (ref "CLS_1") (pin "7") (pinfunction "7_7") (pintype "passive"))
      (node (ref "IC2") (pin "14") (pinfunction "PA0-WKUP_14") (pintype "bidirectional"))
    )
    (net (code "55") (name "PA1") (class "Default")
      (node (ref "ANALOG_IN") (pin "2") (pinfunction "2_2") (pintype "passive"))
      (node (ref "IC2") (pin "15") (pinfunction "PA1_15") (pintype "bidirectional"))
    )
    (net (code "56") (name "PA2") (class "Default")
      (node (ref "ANALOG_IN") (pin "1") (pinfunction "1_1") (pintype "passive"))
      (node (ref "IC2") (pin "16") (pinfunction "PA2_16") (pintype "bidirectional"))
    )
    (net (code "57") (name "PA3") (class "Default")
      (node (ref "CLS_1") (pin "6") (pinfunction "6_6") (pintype "passive"))
      (node (ref "IC2") (pin "17") (pinfunction "PA3_17") (pintype "bidirectional"))
    )
    (net (code "58") (name "PA4") (class "Default")
      (node (ref "CLS_1") (pin "5") (pinfunction "5_5") (pintype "passive"))
      (node (ref "IC2") (pin "20") (pinfunction "PA4_20") (pintype "bidirectional"))
    )
    (net (code "59") (name "PA5") (class "Default")
      (node (ref "CLS_1") (pin "4") (pinfunction "4_4") (pintype "passive"))
      (node (ref "IC2") (pin "21") (pinfunction "PA5_21") (pintype "bidirectional"))
    )
    (net (code "60") (name "PA6") (class "Default")
      (node (ref "CLS_1") (pin "3") (pinfunction "3_3") (pintype "passive"))
      (node (ref "IC2") (pin "22") (pinfunction "PA6_22") (pintype "bidirectional"))
    )
    (net (code "61") (name "PA7") (class "Default")
      (node (ref "CLS_1") (pin "2") (pinfunction "2_2") (pintype "passive"))
      (node (ref "IC2") (pin "23") (pinfunction "PA7_23") (pintype "bidirectional"))
    )
    (net (code "62") (name "PA8{slash}PWM2") (class "Default")
      (node (ref "DIGITAL_PIN_0-7") (pin "6") (pinfunction "6_6") (pintype "passive"))
      (node (ref "IC2") (pin "41") (pinfunction "PA8_41") (pintype "bidirectional"))
    )
    (net (code "63") (name "PB0") (class "Default")
      (node (ref "CLS_2") (pin "3") (pinfunction "3_3") (pintype "passive"))
      (node (ref "IC2") (pin "26") (pinfunction "PB0_26") (pintype "bidirectional"))
    )
    (net (code "64") (name "PB1") (class "Default")
      (node (ref "CLS_2") (pin "2") (pinfunction "2_2") (pintype "passive"))
      (node (ref "IC2") (pin "27") (pinfunction "PB1_27") (pintype "bidirectional"))
    )
    (net (code "65") (name "PB10") (class "Default")
      (node (ref "CLS_2") (pin "1") (pinfunction "1_1") (pintype "passive"))
      (node (ref "IC2") (pin "29") (pinfunction "PB10_29") (pintype "bidirectional"))
    )
    (net (code "66") (name "PB11") (class "Default")
      (node (ref "CLS_3") (pin "4") (pinfunction "4_4") (pintype "passive"))
      (node (ref "IC2") (pin "30") (pinfunction "PB11_30") (pintype "bidirectional"))
    )
    (net (code "67") (name "PB12") (class "Default")
      (node (ref "CLS_3") (pin "3") (pinfunction "3_3") (pintype "passive"))
      (node (ref "IC2") (pin "33") (pinfunction "PB12_33") (pintype "bidirectional"))
    )
    (net (code "68") (name "PB13") (class "Default")
      (node (ref "CLS_3") (pin "2") (pinfunction "2_2") (pintype "passive"))
      (node (ref "IC2") (pin "34") (pinfunction "PB13_34") (pintype "bidirectional"))
    )
    (net (code "69") (name "PB14") (class "Default")
      (node (ref "CLS_3") (pin "1") (pinfunction "1_1") (pintype "passive"))
      (node (ref "IC2") (pin "35") (pinfunction "PB14_35") (pintype "bidirectional"))
    )
    (net (code "70") (name "PB15") (class "Default")
      (node (ref "CLS_4") (pin "4") (pinfunction "4_4") (pintype "passive"))
      (node (ref "IC2") (pin "36") (pinfunction "PB15_36") (pintype "bidirectional"))
    )
    (net (code "71") (name "PC0") (class "Default")
      (node (ref "IC2") (pin "8") (pinfunction "PC0_8") (pintype "bidirectional"))
      (node (ref "JP9") (pin "1") (pinfunction "1_1") (pintype "passive"))
    )
    (net (code "72") (name "PC1") (class "Default")
      (node (ref "IC2") (pin "9") (pinfunction "PC1_9") (pintype "bidirectional"))
      (node (ref "JP6") (pin "1") (pinfunction "1_1") (pintype "passive"))
    )
    (net (code "73") (name "PC2") (class "Default")
      (node (ref "ANALOG_IN") (pin "4") (pinfunction "4_4") (pintype "passive"))
      (node (ref "IC2") (pin "10") (pinfunction "PC2_10") (pintype "bidirectional"))
    )
    (net (code "74") (name "PC3") (class "Default")
      (node (ref "ANALOG_IN") (pin "3") (pinfunction "3_3") (pintype "passive"))
      (node (ref "IC2") (pin "11") (pinfunction "PC3_11") (pintype "bidirectional"))
    )
    (net (code "75") (name "PC4") (class "Default")
      (node (ref "CLS_1") (pin "1") (pinfunction "1_1") (pintype "passive"))
      (node (ref "IC2") (pin "24") (pinfunction "PC4_24") (pintype "bidirectional"))
    )
    (net (code "76") (name "PC5") (class "Default")
      (node (ref "CLS_2") (pin "4") (pinfunction "4_4") (pintype "passive"))
      (node (ref "IC2") (pin "25") (pinfunction "PC5_25") (pintype "bidirectional"))
    )
    (net (code "77") (name "PC6") (class "Default")
      (node (ref "CLS_4") (pin "3") (pinfunction "3_3") (pintype "passive"))
      (node (ref "IC2") (pin "37") (pinfunction "PC6_37") (pintype "bidirectional"))
    )
    (net (code "78") (name "PC7") (class "Default")
      (node (ref "CLS_4") (pin "2") (pinfunction "2_2") (pintype "passive"))
      (node (ref "IC2") (pin "38") (pinfunction "PC7_38") (pintype "bidirectional"))
    )
    (net (code "79") (name "PC8") (class "Default")
      (node (ref "CLS_4") (pin "1") (pinfunction "1_1") (pintype "passive"))
      (node (ref "IC2") (pin "39") (pinfunction "PC8_39") (pintype "bidirectional"))
    )
    (net (code "80") (name "PC9{slash}PWM3") (class "Default")
      (node (ref "DIGITAL_PIN_0-7") (pin "4") (pinfunction "4_4") (pintype "passive"))
      (node (ref "IC2") (pin "40") (pinfunction "PC9_40") (pintype "bidirectional"))
    )
    (net (code "81") (name "PC10") (class "Default")
      (node (ref "DIGITAL_PIN_0-7") (pin "3") (pinfunction "3_3") (pintype "passive"))
      (node (ref "IC2") (pin "51") (pinfunction "PC10_51") (pintype "bidirectional"))
    )
    (net (code "82") (name "PC11") (class "Default")
      (node (ref "DIGITAL_PIN_0-7") (pin "5") (pinfunction "5_5") (pintype "passive"))
      (node (ref "IC2") (pin "52") (pinfunction "PC11_52") (pintype "bidirectional"))
    )
    (net (code "83") (name "PC12") (class "Default")
      (node (ref "DIGITAL_PIN_0-7") (pin "8") (pinfunction "8_8") (pintype "passive"))
      (node (ref "IC2") (pin "53") (pinfunction "PC12_53") (pintype "bidirectional"))
    )
    (net (code "84") (name "PC13") (class "Default")
      (node (ref "CLS_5") (pin "5") (pinfunction "5_5") (pintype "passive"))
      (node (ref "IC2") (pin "2") (pinfunction "PC13_2") (pintype "bidirectional"))
    )
    (net (code "85") (name "PC14") (class "Default")
      (node (ref "C8") (pin "2") (pinfunction "2_2") (pintype "passive"))
      (node (ref "IC2") (pin "3") (pinfunction "PC14_3") (pintype "bidirectional"))
      (node (ref "X_32KHZ") (pin "1") (pinfunction "1_1") (pintype "passive"))
    )
    (net (code "86") (name "PC15") (class "Default")
      (node (ref "IC2") (pin "4") (pinfunction "PC15_4") (pintype "bidirectional"))
      (node (ref "R2") (pin "1") (pinfunction "1_1") (pintype "passive"))
    )
    (net (code "87") (name "PD2") (class "Default")
      (node (ref "DIGITAL_PIN_8-13") (pin "1") (pinfunction "1_1") (pintype "passive"))
      (node (ref "IC2") (pin "54") (pinfunction "PD2_54") (pintype "bidirectional"))
    )
    (net (code "88") (name "PWM4") (class "Default")
      (node (ref "DIGITAL_PIN_8-13") (pin "2") (pinfunction "2_2") (pintype "passive"))
      (node (ref "IC2") (pin "61") (pinfunction "PB8_61") (pintype "bidirectional"))
    )
    (net (code "89") (name "RX") (class "Default")
      (node (ref "DIGITAL_PIN_0-7") (pin "1") (pinfunction "1_1") (pintype "passive"))
      (node (ref "IC2") (pin "43") (pinfunction "PA10_43") (pintype "bidirectional"))
      (node (ref "JP5") (pin "3") (pinfunction "3_3") (pintype "passive"))
    )
    (net (code "90") (name "SCK") (class "Default")
      (node (ref "DIGITAL_PIN_8-13") (pin "6") (pinfunction "6_6") (pintype "passive"))
      (node (ref "IC2") (pin "55") (pinfunction "PB3_55") (pintype "bidirectional"))
    )
    (net (code "91") (name "SCL") (class "Default")
      (node (ref "DIGITAL_PIN_8-13") (pin "10") (pinfunction "10_10") (pintype "passive"))
      (node (ref "IC2") (pin "58") (pinfunction "PB6_58") (pintype "bidirectional"))
      (node (ref "JP9") (pin "3") (pinfunction "3_3") (pintype "passive"))
    )
    (net (code "92") (name "SDA") (class "Default")
      (node (ref "DIGITAL_PIN_8-13") (pin "9") (pinfunction "9_9") (pintype "passive"))
      (node (ref "IC2") (pin "59") (pinfunction "PB7_59") (pintype "bidirectional"))
      (node (ref "JP6") (pin "3") (pinfunction "3_3") (pintype "passive"))
    )
    (net (code "93") (name "SS{slash}PWM5") (class "Default")
      (node (ref "DIGITAL_PIN_8-13") (pin "3") (pinfunction "3_3") (pintype "passive"))
      (node (ref "IC2") (pin "50") (pinfunction "PA15_50") (pintype "bidirectional"))
    )
    (net (code "94") (name "SWCLK") (class "Default")
      (node (ref "IC2") (pin "49") (pinfunction "PA14_49") (pintype "bidirectional"))
      (node (ref "JP7") (pin "1") (pinfunction "1_1") (pintype "passive"))
    )
    (net (code "95") (name "SWDIO") (class "Default")
      (node (ref "IC2") (pin "46") (pinfunction "PA13_46") (pintype "bidirectional"))
      (node (ref "JP7") (pin "3") (pinfunction "3_3") (pintype "passive"))
    )
    (net (code "96") (name "TX") (class "Default")
      (node (ref "DIGITAL_PIN_0-7") (pin "2") (pinfunction "2_2") (pintype "passive"))
      (node (ref "IC2") (pin "42") (pinfunction "PA9_42") (pintype "bidirectional"))
      (node (ref "JP5") (pin "1") (pinfunction "1_1") (pintype "passive"))
    )
    (net (code "97") (name "T_JTCK") (class "Default")
      (node (ref "CLS_5") (pin "3") (pinfunction "3_3") (pintype "passive"))
      (node (ref "IC6") (pin "26") (pinfunction "PB13_26") (pintype "bidirectional"))
      (node (ref "JP7") (pin "2") (pinfunction "2_2") (pintype "passive"))
    )
    (net (code "98") (name "T_JTMS") (class "Default")
      (node (ref "CLS_5") (pin "2") (pinfunction "2_2") (pintype "passive"))
      (node (ref "IC6") (pin "27") (pinfunction "PB14_27") (pintype "bidirectional"))
      (node (ref "JP7") (pin "4") (pinfunction "4_4") (pintype "passive"))
      (node (ref "R21") (pin "1") (pinfunction "1_1") (pintype "passive"))
    )
    (net (code "99") (name "USB_N") (class "Default")
      (node (ref "IC8") (pin "5") (pinfunction "D-_5") (pintype "bidirectional"))
      (node (ref "USB2") (pin "2") (pinfunction "D-_2") (pintype "bidirectional"))
    )
    (net (code "100") (name "USB_P") (class "Default")
      (node (ref "IC8") (pin "4") (pinfunction "D+_4") (pintype "bidirectional"))
      (node (ref "USB2") (pin "3") (pinfunction "D+_3") (pintype "bidirectional"))
    )
    (net (code "101") (name "VBAT") (class "Default")
      (node (ref "C11") (pin "1") (pinfunction "1_1") (pintype "passive"))
      (node (ref "CLS_4") (pin "5") (pinfunction "5_5") (pintype "passive"))
      (node (ref "IC2") (pin "1") (pinfunction "VBAT_1") (pintype "power_in"))
      (node (ref "JP4") (pin "1") (pinfunction "1_1") (pintype "passive"))
    )
    (net (code "102") (name "VDDA") (class "Default")
      (node (ref "C10") (pin "+") (pinfunction "+_+") (pintype "passive"))
      (node (ref "C9") (pin "1") (pinfunction "1_1") (pintype "passive"))
      (node (ref "FB") (pin "2") (pinfunction "2_2") (pintype "passive"))
      (node (ref "IC2") (pin "13") (pinfunction "VDDA_13") (pintype "power_in"))
    )
    (net (code "103") (name "VDDA_PIN") (class "Default")
      (node (ref "DIGITAL_PIN_8-13") (pin "8") (pinfunction "8_8") (pintype "passive"))
      (node (ref "FB") (pin "1") (pinfunction "1_1") (pintype "passive"))
      (node (ref "JP2") (pin "2") (pinfunction "2_2") (pintype "passive"))
    )
    (net (code "104") (name "VIN") (class "Default")
      (node (ref "F1") (pin "2") (pinfunction "2_2") (pintype "passive"))
      (node (ref "J1") (pin "PWR") (pinfunction "PWR_PWR") (pintype "bidirectional"))
      (node (ref "POWER") (pin "8") (pinfunction "8_8") (pintype "passive"))
    )
    (net (code "105") (name "unconnected-(IC6A-PA1-Pad11)") (class "Default")
      (node (ref "IC6") (pin "11") (pinfunction "PA1_11") (pintype "bidirectional"))
    )
    (net (code "106") (name "unconnected-(IC6A-PA2-Pad12)") (class "Default")
      (node (ref "IC6") (pin "12") (pinfunction "PA2_12") (pintype "bidirectional"))
    )
    (net (code "107") (name "unconnected-(IC6A-PA3-Pad13)") (class "Default")
      (node (ref "IC6") (pin "13") (pinfunction "PA3_13") (pintype "bidirectional"))
    )
    (net (code "108") (name "unconnected-(IC6A-PA4-Pad14)") (class "Default")
      (node (ref "IC6") (pin "14") (pinfunction "PA4_14") (pintype "bidirectional"))
    )
    (net (code "109") (name "unconnected-(IC6A-PA5-Pad15)") (class "Default")
      (node (ref "IC6") (pin "15") (pinfunction "PA5_15") (pintype "bidirectional"))
    )
    (net (code "110") (name "unconnected-(IC6A-PA6-Pad16)") (class "Default")
      (node (ref "IC6") (pin "16") (pinfunction "PA6_16") (pintype "bidirectional"))
    )
    (net (code "111") (name "unconnected-(IC6A-PA7-Pad17)") (class "Default")
      (node (ref "IC6") (pin "17") (pinfunction "PA7_17") (pintype "bidirectional"))
    )
    (net (code "112") (name "unconnected-(IC6A-PA8-Pad29)") (class "Default")
      (node (ref "IC6") (pin "29") (pinfunction "PA8_29") (pintype "bidirectional"))
    )
    (net (code "113") (name "unconnected-(IC6A-PA10-Pad31)") (class "Default")
      (node (ref "IC6") (pin "31") (pinfunction "PA10_31") (pintype "bidirectional"))
    )
    (net (code "114") (name "unconnected-(IC6A-PA15-Pad38)") (class "Default")
      (node (ref "IC6") (pin "38") (pinfunction "PA15_38") (pintype "bidirectional"))
    )
    (net (code "115") (name "unconnected-(IC6A-PB0-Pad18)") (class "Default")
      (node (ref "IC6") (pin "18") (pinfunction "PB0_18") (pintype "bidirectional"))
    )
    (net (code "116") (name "unconnected-(IC6A-PB1-Pad19)") (class "Default")
      (node (ref "IC6") (pin "19") (pinfunction "PB1_19") (pintype "bidirectional"))
    )
    (net (code "117") (name "unconnected-(IC6A-PB2-Pad20)") (class "Default")
      (node (ref "IC6") (pin "20") (pinfunction "PB2_20") (pintype "bidirectional"))
    )
    (net (code "118") (name "unconnected-(IC6A-PB3-Pad39)") (class "Default")
      (node (ref "IC6") (pin "39") (pinfunction "PB3_39") (pintype "bidirectional"))
    )
    (net (code "119") (name "unconnected-(IC6A-PB4-Pad40)") (class "Default")
      (node (ref "IC6") (pin "40") (pinfunction "PB4_40") (pintype "bidirectional"))
    )
    (net (code "120") (name "unconnected-(IC6A-PB5-Pad41)") (class "Default")
      (node (ref "IC6") (pin "41") (pinfunction "PB5_41") (pintype "bidirectional"))
    )
    (net (code "121") (name "unconnected-(IC6A-PB6-Pad42)") (class "Default")
      (node (ref "IC6") (pin "42") (pinfunction "PB6_42") (pintype "bidirectional"))
    )
    (net (code "122") (name "unconnected-(IC6A-PB7-Pad43)") (class "Default")
      (node (ref "IC6") (pin "43") (pinfunction "PB7_43") (pintype "bidirectional"))
    )
    (net (code "123") (name "unconnected-(IC6A-PB8-Pad45)") (class "Default")
      (node (ref "IC6") (pin "45") (pinfunction "PB8_45") (pintype "bidirectional"))
    )
    (net (code "124") (name "unconnected-(IC6A-PB9-Pad46)") (class "Default")
      (node (ref "IC6") (pin "46") (pinfunction "PB9_46") (pintype "bidirectional"))
    )
    (net (code "125") (name "unconnected-(IC6A-PB10-Pad21)") (class "Default")
      (node (ref "IC6") (pin "21") (pinfunction "PB10_21") (pintype "bidirectional"))
    )
    (net (code "126") (name "unconnected-(IC6A-PB11-Pad22)") (class "Default")
      (node (ref "IC6") (pin "22") (pinfunction "PB11_22") (pintype "bidirectional"))
    )
    (net (code "127") (name "unconnected-(IC6A-PB15-Pad28)") (class "Default")
      (node (ref "IC6") (pin "28") (pinfunction "PB15_28") (pintype "bidirectional"))
    )
    (net (code "128") (name "unconnected-(IC6A-PC14-Pad3)") (class "Default")
      (node (ref "IC6") (pin "3") (pinfunction "PC14_3") (pintype "bidirectional"))
    )
    (net (code "129") (name "unconnected-(IC6A-PC15-Pad4)") (class "Default")
      (node (ref "IC6") (pin "4") (pinfunction "PC15_4") (pintype "bidirectional"))
    )
    (net (code "130") (name "unconnected-(IC8-CTS-Pad23)") (class "Default")
      (node (ref "IC8") (pin "23") (pinfunction "CTS_23") (pintype "input"))
    )
    (net (code "131") (name "unconnected-(IC8-DCD-Pad1)") (class "Default")
      (node (ref "IC8") (pin "1") (pinfunction "DCD_1") (pintype "input"))
    )
    (net (code "132") (name "unconnected-(IC8-DSR-Pad27)") (class "Default")
      (node (ref "IC8") (pin "27") (pinfunction "DSR_27") (pintype "input"))
    )
    (net (code "133") (name "unconnected-(IC8-DTR-Pad28)") (class "Default")
      (node (ref "IC8") (pin "28") (pinfunction "DTR_28") (pintype "output"))
    )
    (net (code "134") (name "unconnected-(IC8-RI-Pad2)") (class "Default")
      (node (ref "IC8") (pin "2") (pinfunction "RI_2") (pintype "input"))
    )
    (net (code "135") (name "unconnected-(IC8-RTS-Pad24)") (class "Default")
      (node (ref "IC8") (pin "24") (pinfunction "RTS_24") (pintype "output"))
    )
    (net (code "136") (name "unconnected-(IC8-SUSPEND-Pad12)") (class "Default")
      (node (ref "IC8") (pin "12") (pinfunction "SUSPEND_12") (pintype "output"))
    )
    (net (code "137") (name "unconnected-(J1-GNDBREAK-PadGNB)") (class "Default")
      (node (ref "J1") (pin "GNB") (pinfunction "GNDBREAK_GNB") (pintype "bidirectional"))
    )
    (net (code "138") (name "unconnected-(USB1-ID-Pad4)") (class "Default")
      (node (ref "USB1") (pin "4") (pinfunction "ID_4") (pintype "bidirectional"))
    )
    (net (code "139") (name "unconnected-(USB2-ID-Pad4)") (class "Default")
      (node (ref "USB2") (pin "4") (pinfunction "ID_4") (pintype "bidirectional"))
    )
  )
)
